# scaleShield.net
KiCad netlist of a schematic drawn in EAGLE
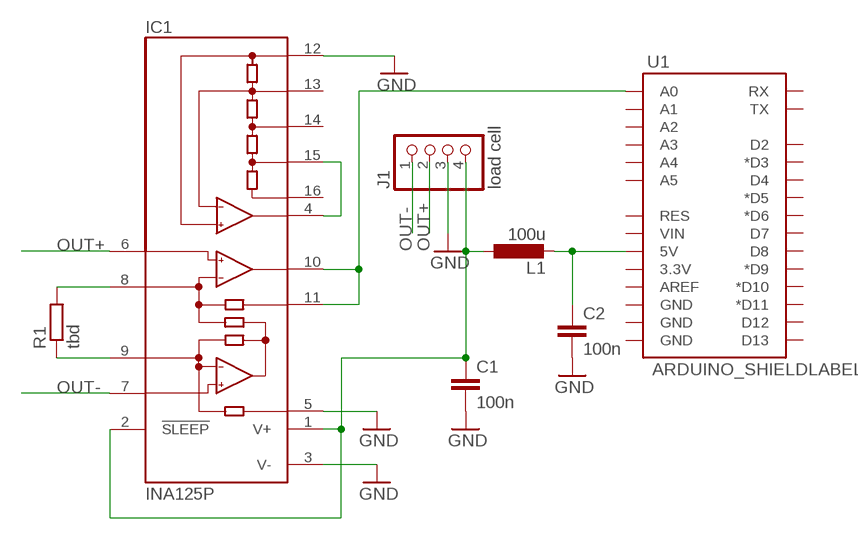
[diagram p0: schematic, sheet 1]

(export (version "E")
  (design (tool "Eeschema 10.0.6"))
  (components
    (comp (ref "C1")
      (value "100n")
      (footprint "eagle-import:C025-025X050")
      (libsource (lib "eagle-import") (part "C-EU025-025X050"))
    )
    (comp (ref "C2")
      (value "100n")
      (footprint "eagle-import:C025-025X050")
      (libsource (lib "eagle-import") (part "C-EU025-025X050"))
    )
    (comp (ref "IC1")
      (value "INA125P")
      (footprint "eagle-import:DIL16")
      (fields (field (name "MF") "TEXAS INSTRUMENT CONNECTORS"))
      (libsource (lib "eagle-import") (part "INA125P"))
    )
    (comp (ref "J1")
      (value "load cell")
      (footprint "eagle-import:1X04")
      (libsource (lib "eagle-import") (part "PINHD-1X4"))
    )
    (comp (ref "L1")
      (value "100u")
      (footprint "eagle-import:0207_10")
      (libsource (lib "eagle-import") (part "L-EU0207/10"))
    )
    (comp (ref "R1")
      (value "tbd")
      (footprint "eagle-import:0207_10")
      (libsource (lib "eagle-import") (part "R-EU_0207/10"))
    )
    (comp (ref "U1")
      (value "ARDUINO_SHIELDLABEL")
      (footprint "eagle-import:DUEMILANOVE_SHIELD")
      (libsource (lib "eagle-import") (part "ARDUINO_SHIELDLABEL"))
    )
  )
  (nets
    (net (code "1") (name "/OUT+") (class "Default")
      (node (ref "IC1") (pin "6") (pinfunction "+IN_6") (pintype "input"))
      (node (ref "J1") (pin "2") (pinfunction "2_2") (pintype "passive"))
    )
    (net (code "2") (name "/OUT-") (class "Default")
      (node (ref "IC1") (pin "7") (pinfunction "-IN_7") (pintype "input"))
      (node (ref "J1") (pin "1") (pinfunction "1_1") (pintype "passive"))
    )
    (net (code "3") (name "GND") (class "Default")
      (node (ref "C1") (pin "2") (pinfunction "2_2") (pintype "passive"))
      (node (ref "C2") (pin "2") (pinfunction "2_2") (pintype "passive"))
      (node (ref "IC1") (pin "12") (pinfunction "REFCOM_12") (pintype "passive"))
      (node (ref "IC1") (pin "3") (pinfunction "V-_3") (pintype "power_in"))
      (node (ref "IC1") (pin "5") (pinfunction "REF_5") (pintype "passive"))
      (node (ref "J1") (pin "3") (pinfunction "3_3") (pintype "passive"))
    )
    (net (code "4") (name "Net-(C2-Pad1)") (class "Default")
      (node (ref "C2") (pin "1") (pinfunction "1_1") (pintype "passive"))
      (node (ref "L1") (pin "2") (pinfunction "2_2") (pintype "passive"))
      (node (ref "U1") (pin "5V") (pinfunction "5V_5V") (pintype "bidirectional"))
    )
    (net (code "5") (name "Net-(IC1-OUT)") (class "Default")
      (node (ref "IC1") (pin "10") (pinfunction "OUT_10") (pintype "output"))
      (node (ref "IC1") (pin "11") (pinfunction "SENSE_11") (pintype "passive"))
      (node (ref "U1") (pin "A0") (pinfunction "A0_A0") (pintype "bidirectional"))
    )
    (net (code "6") (name "Net-(IC1-REF5)") (class "Default")
      (node (ref "IC1") (pin "15") (pinfunction "REF5_15") (pintype "output"))
      (node (ref "IC1") (pin "4") (pinfunction "REFOUT_4") (pintype "output"))
    )
    (net (code "7") (name "Net-(IC1-RG-Pad8)") (class "Default")
      (node (ref "IC1") (pin "8") (pinfunction "RG_8") (pintype "passive"))
      (node (ref "R1") (pin "2") (pinfunction "2_2") (pintype "passive"))
    )
    (net (code "8") (name "Net-(IC1-RG-Pad9)") (class "Default")
      (node (ref "IC1") (pin "9") (pinfunction "RG_9") (pintype "passive"))
      (node (ref "R1") (pin "1") (pinfunction "1_1") (pintype "passive"))
    )
    (net (code "9") (name "Net-(IC1-V+)") (class "Default")
      (node (ref "C1") (pin "1") (pinfunction "1_1") (pintype "passive"))
      (node (ref "IC1") (pin "1") (pinfunction "V+_1") (pintype "power_in"))
      (node (ref "IC1") (pin "2") (pinfunction "~{SLEEP}_2") (pintype "input"))
      (node (ref "J1") (pin "4") (pinfunction "4_4") (pintype "passive"))
      (node (ref "L1") (pin "1") (pinfunction "1_1") (pintype "passive"))
    )
    (net (code "10") (name "unconnected-(IC1-REF2.5-Pad14)") (class "Default")
      (node (ref "IC1") (pin "14") (pinfunction "REF2.5_14") (pintype "output"))
    )
    (net (code "11") (name "unconnected-(IC1-REF10-Pad16)") (class "Default")
      (node (ref "IC1") (pin "16") (pinfunction "REF10_16") (pintype "output"))
    )
    (net (code "12") (name "unconnected-(IC1-REFBG-Pad13)") (class "Default")
      (node (ref "IC1") (pin "13") (pinfunction "REFBG_13") (pintype "output"))
    )
    (net (code "13") (name "unconnected-(U1-*D3-PadD3)") (class "Default")
      (node (ref "U1") (pin "D3") (pinfunction "*D3_D3") (pintype "bidirectional"))
    )
    (net (code "14") (name "unconnected-(U1-*D5-PadD5)") (class "Default")
      (node (ref "U1") (pin "D5") (pinfunction "*D5_D5") (pintype "bidirectional"))
    )
    (net (code "15") (name "unconnected-(U1-*D6-PadD6)") (class "Default")
      (node (ref "U1") (pin "D6") (pinfunction "*D6_D6") (pintype "bidirectional"))
    )
    (net (code "16") (name "unconnected-(U1-*D9-PadD9)") (class "Default")
      (node (ref "U1") (pin "D9") (pinfunction "*D9_D9") (pintype "bidirectional"))
    )
    (net (code "17") (name "unconnected-(U1-*D10-PadD10)") (class "Default")
      (node (ref "U1") (pin "D10") (pinfunction "*D10_D10") (pintype "bidirectional"))
    )
    (net (code "18") (name "unconnected-(U1-*D11-PadD11)") (class "Default")
      (node (ref "U1") (pin "D11") (pinfunction "*D11_D11") (pintype "bidirectional"))
    )
    (net (code "19") (name "unconnected-(U1-GND-PadGND@0)") (class "Default")
      (node (ref "U1") (pin "GND@0") (pinfunction "GND_GND@0") (pintype "bidirectional"))
    )
    (net (code "20") (name "unconnected-(U1-GND-PadGND@1)") (class "Default")
      (node (ref "U1") (pin "GND@1") (pinfunction "GND_GND@1") (pintype "bidirectional"))
    )
    (net (code "21") (name "unconnected-(U1-GND-PadGND@2)") (class "Default")
      (node (ref "U1") (pin "GND@2") (pinfunction "GND_GND@2") (pintype "bidirectional"))
    )
    (net (code "22") (name "unconnected-(U1-Pad3.3V)") (class "Default")
      (node (ref "U1") (pin "3.3V") (pinfunction "3.3V_3.3V") (pintype "bidirectional"))
    )
    (net (code "23") (name "unconnected-(U1-PadA1)") (class "Default")
      (node (ref "U1") (pin "A1") (pinfunction "A1_A1") (pintype "bidirectional"))
    )
    (net (code "24") (name "unconnected-(U1-PadA2)") (class "Default")
      (node (ref "U1") (pin "A2") (pinfunction "A2_A2") (pintype "bidirectional"))
    )
    (net (code "25") (name "unconnected-(U1-PadA3)") (class "Default")
      (node (ref "U1") (pin "A3") (pinfunction "A3_A3") (pintype "bidirectional"))
    )
    (net (code "26") (name "unconnected-(U1-PadA4)") (class "Default")
      (node (ref "U1") (pin "A4") (pinfunction "A4_A4") (pintype "bidirectional"))
    )
    (net (code "27") (name "unconnected-(U1-PadA5)") (class "Default")
      (node (ref "U1") (pin "A5") (pinfunction "A5_A5") (pintype "bidirectional"))
    )
    (net (code "28") (name "unconnected-(U1-PadAREF)") (class "Default")
      (node (ref "U1") (pin "AREF") (pinfunction "AREF_AREF") (pintype "bidirectional"))
    )
    (net (code "29") (name "unconnected-(U1-PadD2)") (class "Default")
      (node (ref "U1") (pin "D2") (pinfunction "D2_D2") (pintype "bidirectional"))
    )
    (net (code "30") (name "unconnected-(U1-PadD4)") (class "Default")
      (node (ref "U1") (pin "D4") (pinfunction "D4_D4") (pintype "bidirectional"))
    )
    (net (code "31") (name "unconnected-(U1-PadD7)") (class "Default")
      (node (ref "U1") (pin "D7") (pinfunction "D7_D7") (pintype "bidirectional"))
    )
    (net (code "32") (name "unconnected-(U1-PadD8)") (class "Default")
      (node (ref "U1") (pin "D8") (pinfunction "D8_D8") (pintype "bidirectional"))
    )
    (net (code "33") (name "unconnected-(U1-PadD12)") (class "Default")
      (node (ref "U1") (pin "D12") (pinfunction "D12_D12") (pintype "bidirectional"))
    )
    (net (code "34") (name "unconnected-(U1-PadD13)") (class "Default")
      (node (ref "U1") (pin "D13") (pinfunction "D13_D13") (pintype "bidirectional"))
    )
    (net (code "35") (name "unconnected-(U1-PadRES)") (class "Default")
      (node (ref "U1") (pin "RES") (pinfunction "RES_RES") (pintype "bidirectional"))
    )
    (net (code "36") (name "unconnected-(U1-PadRX)") (class "Default")
      (node (ref "U1") (pin "RX") (pinfunction "RX_RX") (pintype "bidirectional"))
    )
    (net (code "37") (name "unconnected-(U1-PadTX)") (class "Default")
      (node (ref "U1") (pin "TX") (pinfunction "TX_TX") (pintype "bidirectional"))
    )
    (net (code "38") (name "unconnected-(U1-PadVIN)") (class "Default")
      (node (ref "U1") (pin "VIN") (pinfunction "VIN_VIN") (pintype "bidirectional"))
    )
  )
)
